# ELEC-DEM-555Timer.net
KiCad netlist of a schematic drawn in Altium Designer
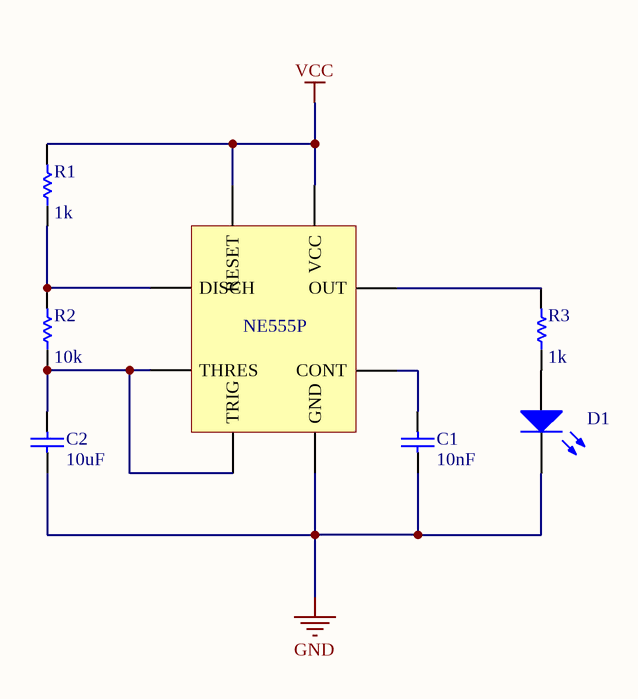
[diagram p0: ELEC-DEM-555Timer.SchDoc]

(export (version "E")
  (design (tool "Eeschema 10.0.6"))
  (components
    (comp (ref "C1")
      (value "10nF")
      (footprint "RAD-0.3")
      (description "Capacitor")
      (fields (field (name "PUBLISHER") "Altium Limited"))
      (libsource (lib "ELEC-DEM-555Timer") (part "10nF"))
    )
    (comp (ref "C2")
      (value "10uF")
      (footprint "RAD-0.3")
      (description "Capacitor")
      (fields (field (name "PUBLISHER") "Altium Limited"))
      (libsource (lib "ELEC-DEM-555Timer") (part "10uF"))
    )
    (comp (ref "D1")
      (value "LED1")
      (footprint "LED-1")
      (description "Typical RED GaAs LED")
      (fields (field (name "PUBLISHER") "Altium Limited"))
      (libsource (lib "ELEC-DEM-555Timer") (part "LED1"))
    )
    (comp (ref "NE555P") (value "NE555P") (libsource (lib "ELEC-DEM-555Timer") (part "NE555P")))
    (comp (ref "R1")
      (value "1k")
      (footprint "AXIAL-0.5")
      (description "1k Resistor")
      (fields (field (name "Comment") "Res Semi") (field (name "PUBLISHER") "Altium Limited"))
      (libsource (lib "ELEC-DEM-555Timer") (part "Res Semi"))
    )
    (comp (ref "R2")
      (value "10k")
      (footprint "AXIAL-0.5")
      (description "10k Resistor")
      (fields (field (name "Comment") "Res Semi_1") (field (name "PUBLISHER") "Altium Limited"))
      (libsource (lib "ELEC-DEM-555Timer") (part "Res Semi_1"))
    )
    (comp (ref "R3")
      (value "1k")
      (footprint "AXIAL-0.5")
      (description "1k Resistor")
      (fields (field (name "Comment") "Res Semi") (field (name "PUBLISHER") "Altium Limited"))
      (libsource (lib "ELEC-DEM-555Timer") (part "Res Semi"))
    )
  )
  (nets
    (net (code "1") (name "GND") (class "Default")
      (node (ref "C1") (pin "1") (pinfunction "1_1") (pintype "passive"))
      (node (ref "C2") (pin "1") (pinfunction "1_1") (pintype "passive"))
      (node (ref "D1") (pin "2") (pinfunction "K_2") (pintype "passive"))
      (node (ref "NE555P") (pin "2") (pinfunction "GND_2") (pintype "passive"))
    )
    (net (code "2") (name "Net-(D1-A)") (class "Default")
      (node (ref "D1") (pin "1") (pinfunction "A_1") (pintype "passive"))
      (node (ref "R3") (pin "1") (pinfunction "1_1") (pintype "passive"))
    )
    (net (code "3") (name "Net-(NE555P-CONT)") (class "Default")
      (node (ref "C1") (pin "2") (pinfunction "2_2") (pintype "passive"))
      (node (ref "NE555P") (pin "2") (pinfunction "CONT_2") (pintype "passive"))
    )
    (net (code "4") (name "Net-(NE555P-DISCH)") (class "Default")
      (node (ref "NE555P") (pin "2") (pinfunction "DISCH_2") (pintype "passive"))
      (node (ref "R1") (pin "1") (pinfunction "1_1") (pintype "passive"))
      (node (ref "R2") (pin "2") (pinfunction "2_2") (pintype "passive"))
    )
    (net (code "5") (name "Net-(NE555P-OUT)") (class "Default")
      (node (ref "NE555P") (pin "2") (pinfunction "OUT_2") (pintype "passive"))
      (node (ref "R3") (pin "2") (pinfunction "2_2") (pintype "passive"))
    )
    (net (code "6") (name "Net-(NE555P-THRES)") (class "Default")
      (node (ref "C2") (pin "2") (pinfunction "2_2") (pintype "passive"))
      (node (ref "NE555P") (pin "2") (pinfunction "THRES_2") (pintype "passive"))
      (node (ref "R2") (pin "1") (pinfunction "1_1") (pintype "passive"))
    )
    (net (code "7") (name "VCC") (class "Default")
      (node (ref "NE555P") (pin "2") (pinfunction "RESET_2") (pintype "passive"))
      (node (ref "R1") (pin "2") (pinfunction "2_2") (pintype "passive"))
    )
  )
)
